# mainboard_reciever_vf0_1.net
KiCad netlist of a schematic drawn in EAGLE
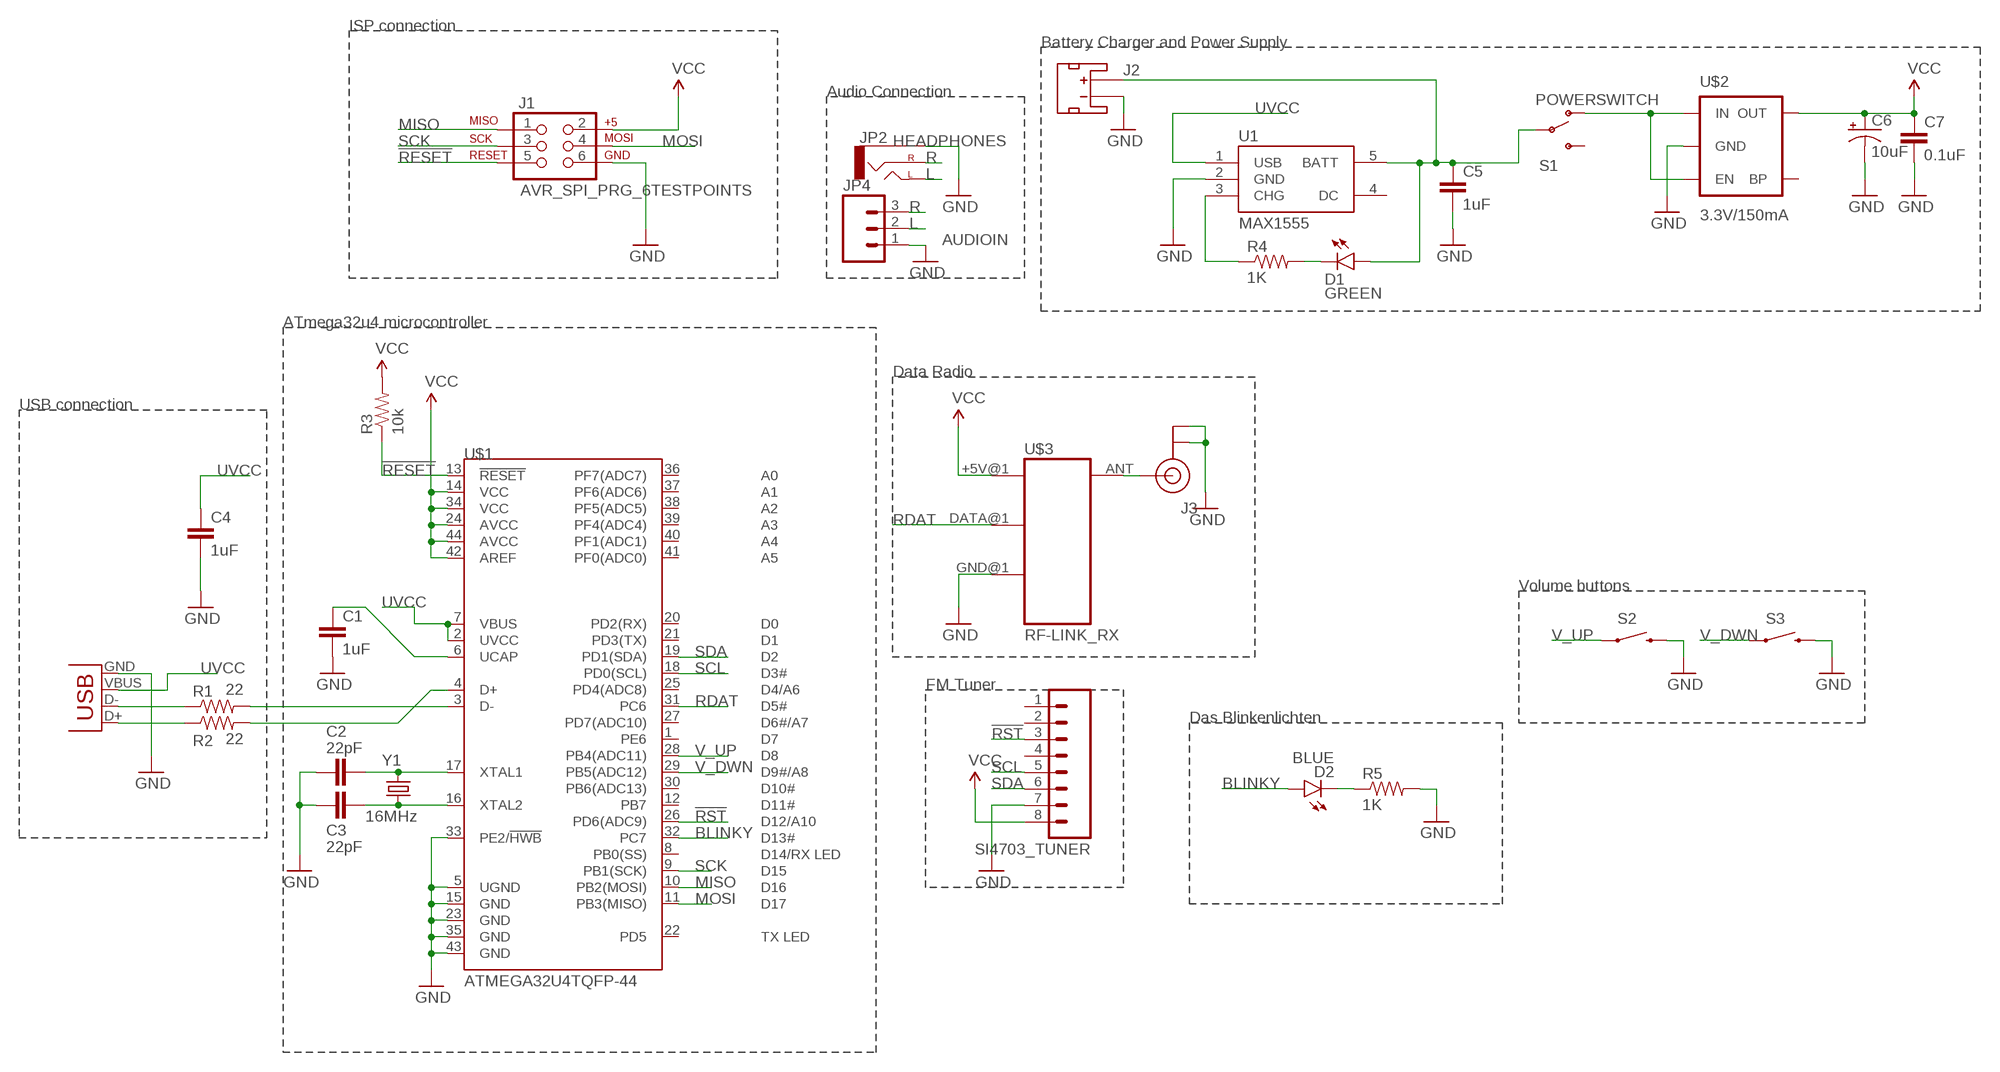
[diagram p0: schematic, sheet 1]

(export (version "E")
  (design (tool "Eeschema 10.0.6"))
  (components
    (comp (ref "C1")
      (value "1uF")
      (footprint "eagle-import:0603-CAP")
      (libsource (lib "eagle-import") (part "CAP0603-CAP"))
    )
    (comp (ref "C2")
      (value "22pF")
      (footprint "eagle-import:0603-CAP")
      (libsource (lib "eagle-import") (part "CAP0603-CAP"))
    )
    (comp (ref "C3")
      (value "22pF")
      (footprint "eagle-import:0603-CAP")
      (libsource (lib "eagle-import") (part "CAP0603-CAP"))
    )
    (comp (ref "C4")
      (value "1uF")
      (footprint "eagle-import:0603-CAP")
      (libsource (lib "eagle-import") (part "CAP0603-CAP"))
    )
    (comp (ref "C5")
      (value "1uF")
      (footprint "eagle-import:0603-CAP")
      (libsource (lib "eagle-import") (part "1.0UF-16V-10%(0603)"))
    )
    (comp (ref "C6")
      (value "10uF")
      (footprint "eagle-import:CPOL-RADIAL-10UF-25V")
      (libsource (lib "eagle-import") (part "10UF-25V-20%(PTH)"))
    )
    (comp (ref "C7")
      (value "0.1uF")
      (footprint "eagle-import:0603-CAP")
      (libsource (lib "eagle-import") (part "0.1UF-25V(+80/-20%)(0603)"))
    )
    (comp (ref "D1")
      (value "GREEN")
      (footprint "eagle-import:LED-0603")
      (libsource (lib "eagle-import") (part "LED-GREEN0603"))
    )
    (comp (ref "D2")
      (value "BLUE")
      (footprint "eagle-import:LED-0603")
      (libsource (lib "eagle-import") (part "LED-BLUE0603"))
    )
    (comp (ref "J1")
      (value "AVR_SPI_PRG_6TESTPOINTS")
      (footprint "eagle-import:2X3_TEST_POINTS")
      (libsource (lib "eagle-import") (part "AVR_SPI_PRG_6TESTPOINTS"))
    )
    (comp (ref "J2")
      (value "BATTERY")
      (footprint "eagle-import:JST-2-SMD")
      (libsource (lib "eagle-import") (part "JST_2MM_MALE"))
    )
    (comp (ref "J3")
      (value "U.FL")
      (footprint "eagle-import:U.FL")
      (libsource (lib "eagle-import") (part "U.FL"))
    )
    (comp (ref "JP1")
      (value "USBSMD")
      (footprint "eagle-import:USB-MINIB")
      (libsource (lib "eagle-import") (part "USBSMD"))
    )
    (comp (ref "JP2")
      (value "HEADPHONES")
      (footprint "eagle-import:AUDIO-JACK")
      (libsource (lib "eagle-import") (part "AUDIO-JACKPTH"))
    )
    (comp (ref "JP4")
      (value "AUDIOIN")
      (footprint "eagle-import:1X03")
      (libsource (lib "eagle-import") (part "M03PTH"))
    )
    (comp (ref "R1")
      (value "22")
      (footprint "eagle-import:0603-RES")
      (libsource (lib "eagle-import") (part "RESISTOR0603"))
    )
    (comp (ref "R2")
      (value "22")
      (footprint "eagle-import:0603-RES")
      (libsource (lib "eagle-import") (part "RESISTOR0603"))
    )
    (comp (ref "R3")
      (value "10k")
      (footprint "eagle-import:0603-RES")
      (libsource (lib "eagle-import") (part "10KOHM1/10W1%(0603)0603"))
    )
    (comp (ref "R4")
      (value "1K")
      (footprint "eagle-import:0603-RES")
      (libsource (lib "eagle-import") (part "1KOHM1/10W1%(0603)"))
    )
    (comp (ref "R5")
      (value "1K")
      (footprint "eagle-import:0603-RES")
      (libsource (lib "eagle-import") (part "1KOHM1/10W1%(0603)"))
    )
    (comp (ref "S1")
      (value "POWERSWITCH")
      (footprint "eagle-import:SWITCH-SPDT-SMD")
      (libsource (lib "eagle-import") (part "SWITCH-SPDTSMD2"))
    )
    (comp (ref "S2")
      (value "SWITCH-MOMENTARY-2SIDE_EZ")
      (footprint "eagle-import:TACTILE-PTH-SIDEEZ")
      (libsource (lib "eagle-import") (part "SWITCH-MOMENTARY-2SIDE_EZ"))
    )
    (comp (ref "S3")
      (value "SWITCH-MOMENTARY-2SIDE_EZ")
      (footprint "eagle-import:TACTILE-PTH-SIDEEZ")
      (libsource (lib "eagle-import") (part "SWITCH-MOMENTARY-2SIDE_EZ"))
    )
    (comp (ref "SI4703_TUNER")
      (value "M08")
      (footprint "eagle-import:1X08_PIN1_NO_SILK")
      (libsource (lib "eagle-import") (part "M08"))
    )
    (comp (ref "U$1")
      (value "ATMEGA32U4TQFP-44")
      (footprint "eagle-import:TQFP44")
      (libsource (lib "eagle-import") (part "ATMEGA32U4TQFP-44"))
    )
    (comp (ref "U$2")
      (value "3.3V/150mA")
      (footprint "eagle-import:SOT23-5")
      (libsource (lib "eagle-import") (part "V_REG_MIC52053.3V"))
    )
    (comp (ref "U$3")
      (value "RF-LINK_RX")
      (footprint "eagle-import:RF-LINK_RX")
      (libsource (lib "eagle-import") (part "RF-LINK_RX"))
    )
    (comp (ref "U1")
      (value "MAX1555")
      (footprint "eagle-import:SOT23-5")
      (libsource (lib "eagle-import") (part "MAX1555"))
    )
    (comp (ref "Y1")
      (value "16MHz")
      (footprint "eagle-import:CRYSTAL-SMD-5X3")
      (libsource (lib "eagle-import") (part "CRYSTAL5X3"))
    )
  )
  (nets
    (net (code "1") (name "/BLINKY") (class "Default")
      (node (ref "D2") (pin "A") (pinfunction "A_A") (pintype "passive"))
      (node (ref "U$1") (pin "32") (pinfunction "PC7_32") (pintype "bidirectional"))
    )
    (net (code "2") (name "/L") (class "Default")
      (node (ref "JP2") (pin "TIP") (pinfunction "LEFT_TIP") (pintype "bidirectional"))
      (node (ref "JP4") (pin "2") (pinfunction "2_2") (pintype "passive"))
    )
    (net (code "3") (name "/MISO") (class "Default")
      (node (ref "J1") (pin "1") (pinfunction "1_1") (pintype "passive"))
      (node (ref "U$1") (pin "10") (pinfunction "PB2(MOSI)_10") (pintype "bidirectional"))
    )
    (net (code "4") (name "/MOSI") (class "Default")
      (node (ref "J1") (pin "4") (pinfunction "4_4") (pintype "passive"))
      (node (ref "U$1") (pin "11") (pinfunction "PB3(MISO)_11") (pintype "bidirectional"))
    )
    (net (code "5") (name "/R") (class "Default")
      (node (ref "JP2") (pin "RING") (pinfunction "RIGHT_RING") (pintype "bidirectional"))
      (node (ref "JP4") (pin "3") (pinfunction "3_3") (pintype "passive"))
    )
    (net (code "6") (name "/RDAT") (class "Default")
      (node (ref "U$1") (pin "31") (pinfunction "PC6_31") (pintype "bidirectional"))
      (node (ref "U$3") (pin "DATA@1") (pinfunction "DATA_DATA@1") (pintype "input"))
    )
    (net (code "7") (name "/SCK") (class "Default")
      (node (ref "J1") (pin "3") (pinfunction "3_3") (pintype "passive"))
      (node (ref "U$1") (pin "9") (pinfunction "PB1(SCK)_9") (pintype "bidirectional"))
    )
    (net (code "8") (name "/SCL") (class "Default")
      (node (ref "SI4703_TUNER") (pin "5") (pinfunction "5_5") (pintype "passive"))
      (node (ref "U$1") (pin "18") (pinfunction "PD0(SCL)_18") (pintype "bidirectional"))
    )
    (net (code "9") (name "/SDA") (class "Default")
      (node (ref "SI4703_TUNER") (pin "6") (pinfunction "6_6") (pintype "passive"))
      (node (ref "U$1") (pin "19") (pinfunction "PD1(SDA)_19") (pintype "bidirectional"))
    )
    (net (code "10") (name "/UVCC") (class "Default")
      (node (ref "C4") (pin "1") (pinfunction "1_1") (pintype "passive"))
      (node (ref "JP1") (pin "VBUS") (pinfunction "VBUS_VBUS") (pintype "bidirectional"))
      (node (ref "U$1") (pin "2") (pinfunction "UVCC_2") (pintype "bidirectional"))
      (node (ref "U$1") (pin "7") (pinfunction "VBUS_7") (pintype "bidirectional"))
      (node (ref "U1") (pin "1") (pinfunction "USB_1") (pintype "bidirectional"))
    )
    (net (code "11") (name "/V_DWN") (class "Default")
      (node (ref "S3") (pin "1") (pinfunction "1_1") (pintype "passive"))
      (node (ref "U$1") (pin "29") (pinfunction "PB5(ADC12)_29") (pintype "bidirectional"))
    )
    (net (code "12") (name "/V_UP") (class "Default")
      (node (ref "S2") (pin "1") (pinfunction "1_1") (pintype "passive"))
      (node (ref "U$1") (pin "28") (pinfunction "PB4(ADC11)_28") (pintype "bidirectional"))
    )
    (net (code "13") (name "/~{RESET}") (class "Default")
      (node (ref "J1") (pin "5") (pinfunction "5_5") (pintype "passive"))
      (node (ref "R3") (pin "1") (pinfunction "1_1") (pintype "passive"))
      (node (ref "U$1") (pin "13") (pinfunction "~{RESET}_13") (pintype "bidirectional"))
    )
    (net (code "14") (name "/~{RST}") (class "Default")
      (node (ref "SI4703_TUNER") (pin "3") (pinfunction "3_3") (pintype "passive"))
      (node (ref "U$1") (pin "26") (pinfunction "PD6(ADC9)_26") (pintype "bidirectional"))
    )
    (net (code "15") (name "GND") (class "Default")
      (node (ref "C1") (pin "2") (pinfunction "2_2") (pintype "passive"))
      (node (ref "C2") (pin "1") (pinfunction "1_1") (pintype "passive"))
      (node (ref "C3") (pin "1") (pinfunction "1_1") (pintype "passive"))
      (node (ref "C4") (pin "2") (pinfunction "2_2") (pintype "passive"))
      (node (ref "C5") (pin "2") (pinfunction "2_2") (pintype "passive"))
      (node (ref "C6") (pin "2") (pinfunction "-_2") (pintype "passive"))
      (node (ref "C7") (pin "2") (pinfunction "2_2") (pintype "passive"))
      (node (ref "J1") (pin "6") (pinfunction "6_6") (pintype "passive"))
      (node (ref "J2") (pin "1") (pinfunction "-_1") (pintype "bidirectional"))
      (node (ref "J3") (pin "P$1") (pinfunction "GND_P$1") (pintype "bidirectional"))
      (node (ref "J3") (pin "P$2") (pinfunction "GND_P$2") (pintype "bidirectional"))
      (node (ref "JP1") (pin "GND") (pinfunction "GND_GND") (pintype "bidirectional"))
      (node (ref "JP2") (pin "SLEEVE") (pinfunction "SLEEVE_SLEEVE") (pintype "bidirectional"))
      (node (ref "JP4") (pin "1") (pinfunction "1_1") (pintype "passive"))
      (node (ref "R5") (pin "2") (pinfunction "2_2") (pintype "passive"))
      (node (ref "S2") (pin "2") (pinfunction "2_2") (pintype "passive"))
      (node (ref "S3") (pin "2") (pinfunction "2_2") (pintype "passive"))
      (node (ref "SI4703_TUNER") (pin "7") (pinfunction "7_7") (pintype "passive"))
      (node (ref "U$1") (pin "15") (pinfunction "GND_15") (pintype "bidirectional"))
      (node (ref "U$1") (pin "23") (pinfunction "GND_23") (pintype "bidirectional"))
      (node (ref "U$1") (pin "33") (pinfunction "PE2/~{HWB}_33") (pintype "bidirectional"))
      (node (ref "U$1") (pin "35") (pinfunction "GND_35") (pintype "bidirectional"))
      (node (ref "U$1") (pin "43") (pinfunction "GND_43") (pintype "bidirectional"))
      (node (ref "U$1") (pin "5") (pinfunction "UGND_5") (pintype "bidirectional"))
      (node (ref "U$2") (pin "2") (pinfunction "GND_2") (pintype "input"))
      (node (ref "U$3") (pin "GND@1") (pinfunction "GND_GND@1") (pintype "power_in"))
      (node (ref "U1") (pin "2") (pinfunction "GND_2") (pintype "bidirectional"))
    )
    (net (code "16") (name "Net-(D1-PadC)") (class "Default")
      (node (ref "D1") (pin "C") (pinfunction "C_C") (pintype "passive"))
      (node (ref "R4") (pin "2") (pinfunction "2_2") (pintype "passive"))
    )
    (net (code "17") (name "Net-(D2-PadC)") (class "Default")
      (node (ref "D2") (pin "C") (pinfunction "C_C") (pintype "passive"))
      (node (ref "R5") (pin "1") (pinfunction "1_1") (pintype "passive"))
    )
    (net (code "18") (name "Net-(J2-+)") (class "Default")
      (node (ref "C5") (pin "1") (pinfunction "1_1") (pintype "passive"))
      (node (ref "D1") (pin "A") (pinfunction "A_A") (pintype "passive"))
      (node (ref "J2") (pin "2") (pinfunction "+_2") (pintype "bidirectional"))
      (node (ref "S1") (pin "2") (pinfunction "P_2") (pintype "passive"))
      (node (ref "U1") (pin "5") (pinfunction "BATT_5") (pintype "bidirectional"))
    )
    (net (code "19") (name "Net-(J3-SIGNAL)") (class "Default")
      (node (ref "J3") (pin "P$3") (pinfunction "SIGNAL_P$3") (pintype "bidirectional"))
      (node (ref "U$3") (pin "ANT") (pinfunction "ANT_ANT") (pintype "passive"))
    )
    (net (code "20") (name "Net-(JP1-PadD+)") (class "Default")
      (node (ref "JP1") (pin "D+") (pinfunction "D+_D+") (pintype "bidirectional"))
      (node (ref "R2") (pin "1") (pinfunction "1_1") (pintype "passive"))
    )
    (net (code "21") (name "Net-(JP1-PadD-)") (class "Default")
      (node (ref "JP1") (pin "D-") (pinfunction "D-_D-") (pintype "bidirectional"))
      (node (ref "R1") (pin "1") (pinfunction "1_1") (pintype "passive"))
    )
    (net (code "22") (name "Net-(S1-O)") (class "Default")
      (node (ref "S1") (pin "1") (pinfunction "O_1") (pintype "passive"))
      (node (ref "U$2") (pin "1") (pinfunction "IN_1") (pintype "input"))
      (node (ref "U$2") (pin "3") (pinfunction "EN_3") (pintype "input"))
    )
    (net (code "23") (name "Net-(U$1-D+)") (class "Default")
      (node (ref "R2") (pin "2") (pinfunction "2_2") (pintype "passive"))
      (node (ref "U$1") (pin "4") (pinfunction "D+_4") (pintype "bidirectional"))
    )
    (net (code "24") (name "Net-(U$1-D-)") (class "Default")
      (node (ref "R1") (pin "2") (pinfunction "2_2") (pintype "passive"))
      (node (ref "U$1") (pin "3") (pinfunction "D-_3") (pintype "bidirectional"))
    )
    (net (code "25") (name "Net-(U$1-UCAP)") (class "Default")
      (node (ref "C1") (pin "1") (pinfunction "1_1") (pintype "passive"))
      (node (ref "U$1") (pin "6") (pinfunction "UCAP_6") (pintype "bidirectional"))
    )
    (net (code "26") (name "Net-(U$1-XTAL1)") (class "Default")
      (node (ref "C2") (pin "2") (pinfunction "2_2") (pintype "passive"))
      (node (ref "U$1") (pin "17") (pinfunction "XTAL1_17") (pintype "bidirectional"))
      (node (ref "Y1") (pin "3") (pinfunction "2_3") (pintype "passive"))
    )
    (net (code "27") (name "Net-(U$1-XTAL2)") (class "Default")
      (node (ref "C3") (pin "2") (pinfunction "2_2") (pintype "passive"))
      (node (ref "U$1") (pin "16") (pinfunction "XTAL2_16") (pintype "bidirectional"))
      (node (ref "Y1") (pin "1") (pinfunction "1_1") (pintype "passive"))
    )
    (net (code "28") (name "Net-(U1-CHG)") (class "Default")
      (node (ref "R4") (pin "1") (pinfunction "1_1") (pintype "passive"))
      (node (ref "U1") (pin "3") (pinfunction "CHG_3") (pintype "bidirectional"))
    )
    (net (code "29") (name "VCC") (class "Default")
      (node (ref "C6") (pin "1") (pinfunction "+_1") (pintype "passive"))
      (node (ref "C7") (pin "1") (pinfunction "1_1") (pintype "passive"))
      (node (ref "J1") (pin "2") (pinfunction "2_2") (pintype "passive"))
      (node (ref "R3") (pin "2") (pinfunction "2_2") (pintype "passive"))
      (node (ref "SI4703_TUNER") (pin "8") (pinfunction "8_8") (pintype "passive"))
      (node (ref "U$1") (pin "14") (pinfunction "VCC_14") (pintype "bidirectional"))
      (node (ref "U$1") (pin "24") (pinfunction "AVCC_24") (pintype "bidirectional"))
      (node (ref "U$1") (pin "34") (pinfunction "VCC_34") (pintype "bidirectional"))
      (node (ref "U$1") (pin "42") (pinfunction "AREF_42") (pintype "bidirectional"))
      (node (ref "U$1") (pin "44") (pinfunction "AVCC_44") (pintype "bidirectional"))
      (node (ref "U$2") (pin "5") (pinfunction "OUT_5") (pintype "passive"))
      (node (ref "U$3") (pin "+5V@1") (pinfunction "+5V_+5V@1") (pintype "power_in"))
    )
    (net (code "30") (name "unconnected-(J2-PAD1-PadNC1)") (class "Default")
      (node (ref "J2") (pin "NC1") (pinfunction "PAD1_NC1") (pintype "bidirectional"))
    )
    (net (code "31") (name "unconnected-(J2-PAD2-PadNC2)") (class "Default")
      (node (ref "J2") (pin "NC2") (pinfunction "PAD2_NC2") (pintype "bidirectional"))
    )
    (net (code "32") (name "unconnected-(S1-S-Pad3)") (class "Default")
      (node (ref "S1") (pin "3") (pinfunction "S_3") (pintype "passive"))
    )
    (net (code "33") (name "unconnected-(SI4703_TUNER-Pad1)") (class "Default")
      (node (ref "SI4703_TUNER") (pin "1") (pinfunction "1_1") (pintype "passive"))
    )
    (net (code "34") (name "unconnected-(SI4703_TUNER-Pad2)") (class "Default")
      (node (ref "SI4703_TUNER") (pin "2") (pinfunction "2_2") (pintype "passive"))
    )
    (net (code "35") (name "unconnected-(SI4703_TUNER-Pad4)") (class "Default")
      (node (ref "SI4703_TUNER") (pin "4") (pinfunction "4_4") (pintype "passive"))
    )
    (net (code "36") (name "unconnected-(U$1-PB0(SS)-Pad8)") (class "Default")
      (node (ref "U$1") (pin "8") (pinfunction "PB0(SS)_8") (pintype "bidirectional"))
    )
    (net (code "37") (name "unconnected-(U$1-PB6(ADC13)-Pad30)") (class "Default")
      (node (ref "U$1") (pin "30") (pinfunction "PB6(ADC13)_30") (pintype "bidirectional"))
    )
    (net (code "38") (name "unconnected-(U$1-PB7-Pad12)") (class "Default")
      (node (ref "U$1") (pin "12") (pinfunction "PB7_12") (pintype "bidirectional"))
    )
    (net (code "39") (name "unconnected-(U$1-PD2(RX)-Pad20)") (class "Default")
      (node (ref "U$1") (pin "20") (pinfunction "PD2(RX)_20") (pintype "bidirectional"))
    )
    (net (code "40") (name "unconnected-(U$1-PD3(TX)-Pad21)") (class "Default")
      (node (ref "U$1") (pin "21") (pinfunction "PD3(TX)_21") (pintype "bidirectional"))
    )
    (net (code "41") (name "unconnected-(U$1-PD4(ADC8)-Pad25)") (class "Default")
      (node (ref "U$1") (pin "25") (pinfunction "PD4(ADC8)_25") (pintype "bidirectional"))
    )
    (net (code "42") (name "unconnected-(U$1-PD5-Pad22)") (class "Default")
      (node (ref "U$1") (pin "22") (pinfunction "PD5_22") (pintype "bidirectional"))
    )
    (net (code "43") (name "unconnected-(U$1-PD7(ADC10)-Pad27)") (class "Default")
      (node (ref "U$1") (pin "27") (pinfunction "PD7(ADC10)_27") (pintype "bidirectional"))
    )
    (net (code "44") (name "unconnected-(U$1-PE6-Pad1)") (class "Default")
      (node (ref "U$1") (pin "1") (pinfunction "PE6_1") (pintype "bidirectional"))
    )
    (net (code "45") (name "unconnected-(U$1-PF0(ADC0)-Pad41)") (class "Default")
      (node (ref "U$1") (pin "41") (pinfunction "PF0(ADC0)_41") (pintype "bidirectional"))
    )
    (net (code "46") (name "unconnected-(U$1-PF1(ADC1)-Pad40)") (class "Default")
      (node (ref "U$1") (pin "40") (pinfunction "PF1(ADC1)_40") (pintype "bidirectional"))
    )
    (net (code "47") (name "unconnected-(U$1-PF4(ADC4)-Pad39)") (class "Default")
      (node (ref "U$1") (pin "39") (pinfunction "PF4(ADC4)_39") (pintype "bidirectional"))
    )
    (net (code "48") (name "unconnected-(U$1-PF5(ADC5)-Pad38)") (class "Default")
      (node (ref "U$1") (pin "38") (pinfunction "PF5(ADC5)_38") (pintype "bidirectional"))
    )
    (net (code "49") (name "unconnected-(U$1-PF6(ADC6)-Pad37)") (class "Default")
      (node (ref "U$1") (pin "37") (pinfunction "PF6(ADC6)_37") (pintype "bidirectional"))
    )
    (net (code "50") (name "unconnected-(U$1-PF7(ADC7)-Pad36)") (class "Default")
      (node (ref "U$1") (pin "36") (pinfunction "PF7(ADC7)_36") (pintype "bidirectional"))
    )
    (net (code "51") (name "unconnected-(U$2-BP-Pad4)") (class "Default")
      (node (ref "U$2") (pin "4") (pinfunction "BP_4") (pintype "input"))
    )
    (net (code "52") (name "unconnected-(U1-DC-Pad4)") (class "Default")
      (node (ref "U1") (pin "4") (pinfunction "DC_4") (pintype "bidirectional"))
    )
  )
)
